# MD_plate.net
KiCad netlist of a schematic drawn in EAGLE
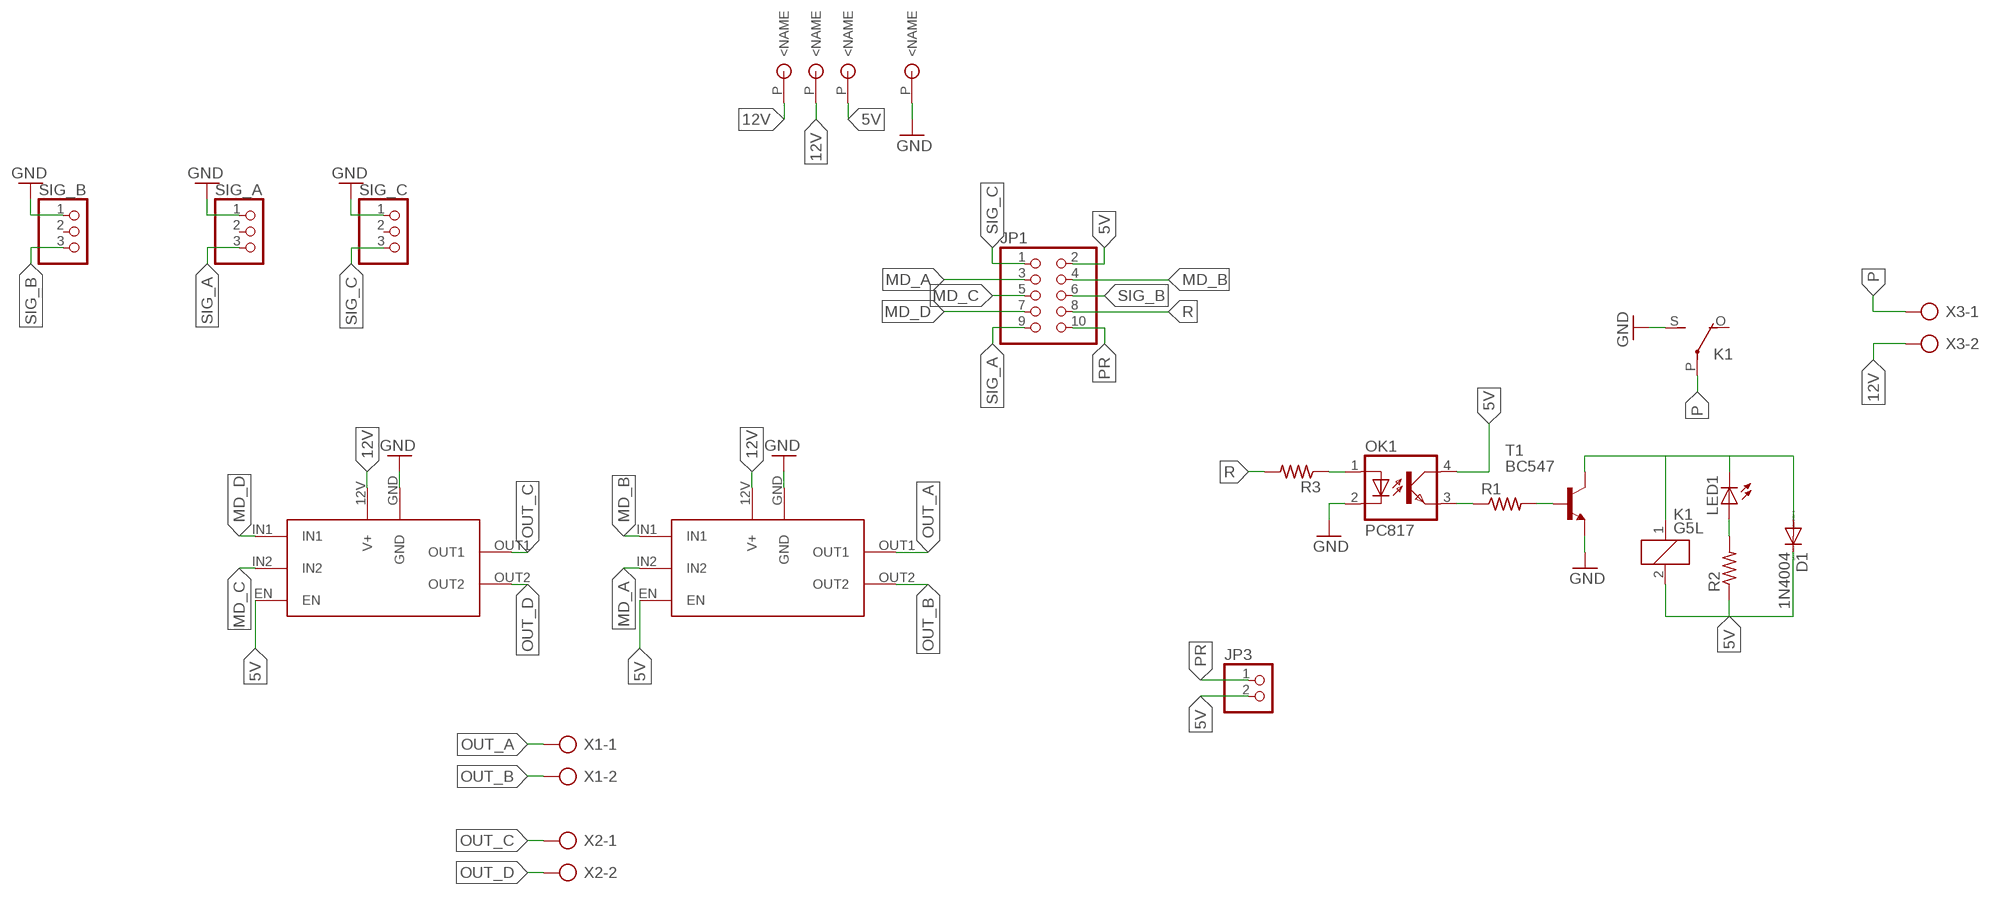
[diagram p0: schematic, sheet 1]

(export (version "E")
  (design (tool "Eeschema 10.0.6"))
  (components
    (comp (ref "6")
      (value "CU-SPACER")
      (footprint "eagle-import:CU-SPACER")
      (libsource (lib "eagle-import") (part "CU-SPACER"))
    )
    (comp (ref "12_A")
      (value "CU-SPACER")
      (footprint "eagle-import:CU-SPACER")
      (libsource (lib "eagle-import") (part "CU-SPACER"))
    )
    (comp (ref "12_B")
      (value "CU-SPACER")
      (footprint "eagle-import:CU-SPACER")
      (libsource (lib "eagle-import") (part "CU-SPACER"))
    )
    (comp (ref "D1")
      (value "1N4004")
      (footprint "eagle-import:DO41-10")
      (libsource (lib "eagle-import") (part "1N4004"))
    )
    (comp (ref "JP1")
      (value "PINHD-2X5")
      (footprint "eagle-import:2X05")
      (libsource (lib "eagle-import") (part "PINHD-2X5"))
    )
    (comp (ref "JP3")
      (value "PINHD-1X2")
      (footprint "eagle-import:1X02")
      (libsource (lib "eagle-import") (part "PINHD-1X2"))
    )
    (comp (ref "K1")
      (value "G5L")
      (footprint "eagle-import:G5LE")
      (libsource (lib "eagle-import") (part "G5L"))
    )
    (comp (ref "LED1")
      (value "LED3MM")
      (footprint "eagle-import:LED3MM")
      (libsource (lib "eagle-import") (part "LED3MM"))
    )
    (comp (ref "OK1")
      (value "PC817")
      (footprint "eagle-import:DIL04")
      (fields (field (name "MPN") "PC817X4J000F"))
      (libsource (lib "eagle-import") (part "PC817"))
    )
    (comp (ref "R1")
      (value "R-US_0204/7")
      (footprint "eagle-import:0204_7")
      (libsource (lib "eagle-import") (part "R-US_0204/7"))
    )
    (comp (ref "R2")
      (value "R-US_0204/7")
      (footprint "eagle-import:0204_7")
      (libsource (lib "eagle-import") (part "R-US_0204/7"))
    )
    (comp (ref "R3")
      (value "R-US_0204/7")
      (footprint "eagle-import:0204_7")
      (libsource (lib "eagle-import") (part "R-US_0204/7"))
    )
    (comp (ref "SIG_A")
      (value "PINHD-1X3/90")
      (footprint "eagle-import:1X03_90")
      (libsource (lib "eagle-import") (part "PINHD-1X3/90"))
    )
    (comp (ref "SIG_B")
      (value "PINHD-1X3/90")
      (footprint "eagle-import:1X03_90")
      (libsource (lib "eagle-import") (part "PINHD-1X3/90"))
    )
    (comp (ref "SIG_C")
      (value "PINHD-1X3/90")
      (footprint "eagle-import:1X03_90")
      (libsource (lib "eagle-import") (part "PINHD-1X3/90"))
    )
    (comp (ref "T1")
      (value "BC547")
      (footprint "eagle-import:TO92")
      (libsource (lib "eagle-import") (part "BC547"))
    )
    (comp (ref "U$1")
      (value "L6203-MODULE")
      (footprint "eagle-import:L6203-MODULE")
      (libsource (lib "eagle-import") (part "L6203-MODULE"))
    )
    (comp (ref "U$2")
      (value "L6203-MODULE")
      (footprint "eagle-import:L6203-MODULE")
      (libsource (lib "eagle-import") (part "L6203-MODULE"))
    )
    (comp (ref "U$6")
      (value "CU-SPACER")
      (footprint "eagle-import:CU-SPACER")
      (libsource (lib "eagle-import") (part "CU-SPACER"))
    )
    (comp (ref "X1")
      (value "AK500/2")
      (footprint "eagle-import:AK500_2")
      (libsource (lib "eagle-import") (part "AK500/2"))
    )
    (comp (ref "X2")
      (value "AK500/2")
      (footprint "eagle-import:AK500_2")
      (libsource (lib "eagle-import") (part "AK500/2"))
    )
    (comp (ref "X3")
      (value "AK500/2")
      (footprint "eagle-import:AK500_2")
      (libsource (lib "eagle-import") (part "AK500/2"))
    )
  )
  (nets
    (net (code "1") (name "5V") (class "Default")
      (node (ref "6") (pin "P") (pinfunction "<NAME_P") (pintype "bidirectional"))
      (node (ref "D1") (pin "C") (pinfunction "C_C") (pintype "passive"))
      (node (ref "JP1") (pin "2") (pinfunction "2_2") (pintype "passive"))
      (node (ref "JP3") (pin "2") (pinfunction "2_2") (pintype "passive"))
      (node (ref "K1") (pin "2") (pinfunction "2_2") (pintype "passive"))
      (node (ref "OK1") (pin "4") (pinfunction "COL_4") (pintype "passive"))
      (node (ref "R2") (pin "1") (pinfunction "1_1") (pintype "passive"))
      (node (ref "U$1") (pin "EN") (pinfunction "EN_EN") (pintype "bidirectional"))
      (node (ref "U$2") (pin "EN") (pinfunction "EN_EN") (pintype "bidirectional"))
    )
    (net (code "2") (name "12V") (class "Default")
      (node (ref "12_A") (pin "P") (pinfunction "<NAME_P") (pintype "bidirectional"))
      (node (ref "12_B") (pin "P") (pinfunction "<NAME_P") (pintype "bidirectional"))
      (node (ref "U$1") (pin "12V") (pinfunction "V+_12V") (pintype "bidirectional"))
      (node (ref "U$2") (pin "12V") (pinfunction "V+_12V") (pintype "bidirectional"))
      (node (ref "X3") (pin "2") (pinfunction "KL_2") (pintype "passive"))
    )
    (net (code "3") (name "GND") (class "Default")
      (node (ref "K1") (pin "S") (pinfunction "S_S") (pintype "passive"))
      (node (ref "OK1") (pin "2") (pinfunction "C_2") (pintype "passive"))
      (node (ref "SIG_A") (pin "1") (pinfunction "1_1") (pintype "passive"))
      (node (ref "SIG_B") (pin "1") (pinfunction "1_1") (pintype "passive"))
      (node (ref "SIG_C") (pin "1") (pinfunction "1_1") (pintype "passive"))
      (node (ref "T1") (pin "1") (pinfunction "E_1") (pintype "passive"))
      (node (ref "U$1") (pin "GND") (pinfunction "GND_GND") (pintype "bidirectional"))
      (node (ref "U$2") (pin "GND") (pinfunction "GND_GND") (pintype "bidirectional"))
      (node (ref "U$6") (pin "P") (pinfunction "<NAME_P") (pintype "bidirectional"))
    )
    (net (code "4") (name "MD_A") (class "Default")
      (node (ref "JP1") (pin "3") (pinfunction "3_3") (pintype "passive"))
      (node (ref "U$2") (pin "IN2") (pinfunction "IN2_IN2") (pintype "bidirectional"))
    )
    (net (code "5") (name "MD_B") (class "Default")
      (node (ref "JP1") (pin "4") (pinfunction "4_4") (pintype "passive"))
      (node (ref "U$2") (pin "IN1") (pinfunction "IN1_IN1") (pintype "bidirectional"))
    )
    (net (code "6") (name "MD_C") (class "Default")
      (node (ref "JP1") (pin "5") (pinfunction "5_5") (pintype "passive"))
      (node (ref "U$1") (pin "IN2") (pinfunction "IN2_IN2") (pintype "bidirectional"))
    )
    (net (code "7") (name "MD_D") (class "Default")
      (node (ref "JP1") (pin "7") (pinfunction "7_7") (pintype "passive"))
      (node (ref "U$1") (pin "IN1") (pinfunction "IN1_IN1") (pintype "bidirectional"))
    )
    (net (code "8") (name "Net-(LED1-C)") (class "Default")
      (node (ref "D1") (pin "A") (pinfunction "A_A") (pintype "passive"))
      (node (ref "K1") (pin "1") (pinfunction "1_1") (pintype "passive"))
      (node (ref "LED1") (pin "K") (pinfunction "C_K") (pintype "passive"))
      (node (ref "T1") (pin "3") (pinfunction "C_3") (pintype "passive"))
    )
    (net (code "9") (name "Net-(LED1-PadA)") (class "Default")
      (node (ref "LED1") (pin "A") (pinfunction "A_A") (pintype "passive"))
      (node (ref "R2") (pin "2") (pinfunction "2_2") (pintype "passive"))
    )
    (net (code "10") (name "Net-(OK1-A)") (class "Default")
      (node (ref "OK1") (pin "1") (pinfunction "A_1") (pintype "passive"))
      (node (ref "R3") (pin "1") (pinfunction "1_1") (pintype "passive"))
    )
    (net (code "11") (name "Net-(OK1-EMIT)") (class "Default")
      (node (ref "OK1") (pin "3") (pinfunction "EMIT_3") (pintype "passive"))
      (node (ref "R1") (pin "1") (pinfunction "1_1") (pintype "passive"))
    )
    (net (code "12") (name "Net-(T1-B)") (class "Default")
      (node (ref "R1") (pin "2") (pinfunction "2_2") (pintype "passive"))
      (node (ref "T1") (pin "2") (pinfunction "B_2") (pintype "passive"))
    )
    (net (code "13") (name "OUT_A") (class "Default")
      (node (ref "U$2") (pin "OUT1") (pinfunction "OUT1_OUT1") (pintype "bidirectional"))
      (node (ref "X1") (pin "1") (pinfunction "KL_1") (pintype "passive"))
    )
    (net (code "14") (name "OUT_B") (class "Default")
      (node (ref "U$2") (pin "OUT2") (pinfunction "OUT2_OUT2") (pintype "bidirectional"))
      (node (ref "X1") (pin "2") (pinfunction "KL_2") (pintype "passive"))
    )
    (net (code "15") (name "OUT_C") (class "Default")
      (node (ref "U$1") (pin "OUT1") (pinfunction "OUT1_OUT1") (pintype "bidirectional"))
      (node (ref "X2") (pin "1") (pinfunction "KL_1") (pintype "passive"))
    )
    (net (code "16") (name "OUT_D") (class "Default")
      (node (ref "U$1") (pin "OUT2") (pinfunction "OUT2_OUT2") (pintype "bidirectional"))
      (node (ref "X2") (pin "2") (pinfunction "KL_2") (pintype "passive"))
    )
    (net (code "17") (name "P") (class "Default")
      (node (ref "K1") (pin "P") (pinfunction "P_P") (pintype "passive"))
      (node (ref "X3") (pin "1") (pinfunction "KL_1") (pintype "passive"))
    )
    (net (code "18") (name "PR") (class "Default")
      (node (ref "JP1") (pin "10") (pinfunction "10_10") (pintype "passive"))
      (node (ref "JP3") (pin "1") (pinfunction "1_1") (pintype "passive"))
    )
    (net (code "19") (name "R") (class "Default")
      (node (ref "JP1") (pin "8") (pinfunction "8_8") (pintype "passive"))
      (node (ref "R3") (pin "2") (pinfunction "2_2") (pintype "passive"))
    )
    (net (code "20") (name "SIG_A") (class "Default")
      (node (ref "JP1") (pin "9") (pinfunction "9_9") (pintype "passive"))
      (node (ref "SIG_A") (pin "3") (pinfunction "3_3") (pintype "passive"))
    )
    (net (code "21") (name "SIG_B") (class "Default")
      (node (ref "JP1") (pin "6") (pinfunction "6_6") (pintype "passive"))
      (node (ref "SIG_B") (pin "3") (pinfunction "3_3") (pintype "passive"))
    )
    (net (code "22") (name "SIG_C") (class "Default")
      (node (ref "JP1") (pin "1") (pinfunction "1_1") (pintype "passive"))
      (node (ref "SIG_C") (pin "3") (pinfunction "3_3") (pintype "passive"))
    )
    (net (code "23") (name "unconnected-(K1-PadO)") (class "Default")
      (node (ref "K1") (pin "O") (pinfunction "O_O") (pintype "passive"))
    )
    (net (code "24") (name "unconnected-(SIG_A-Pad2)") (class "Default")
      (node (ref "SIG_A") (pin "2") (pinfunction "2_2") (pintype "passive"))
    )
    (net (code "25") (name "unconnected-(SIG_B-Pad2)") (class "Default")
      (node (ref "SIG_B") (pin "2") (pinfunction "2_2") (pintype "passive"))
    )
    (net (code "26") (name "unconnected-(SIG_C-Pad2)") (class "Default")
      (node (ref "SIG_C") (pin "2") (pinfunction "2_2") (pintype "passive"))
    )
  )
)
